# switches_relay.net
KiCad netlist of a schematic drawn in EAGLE
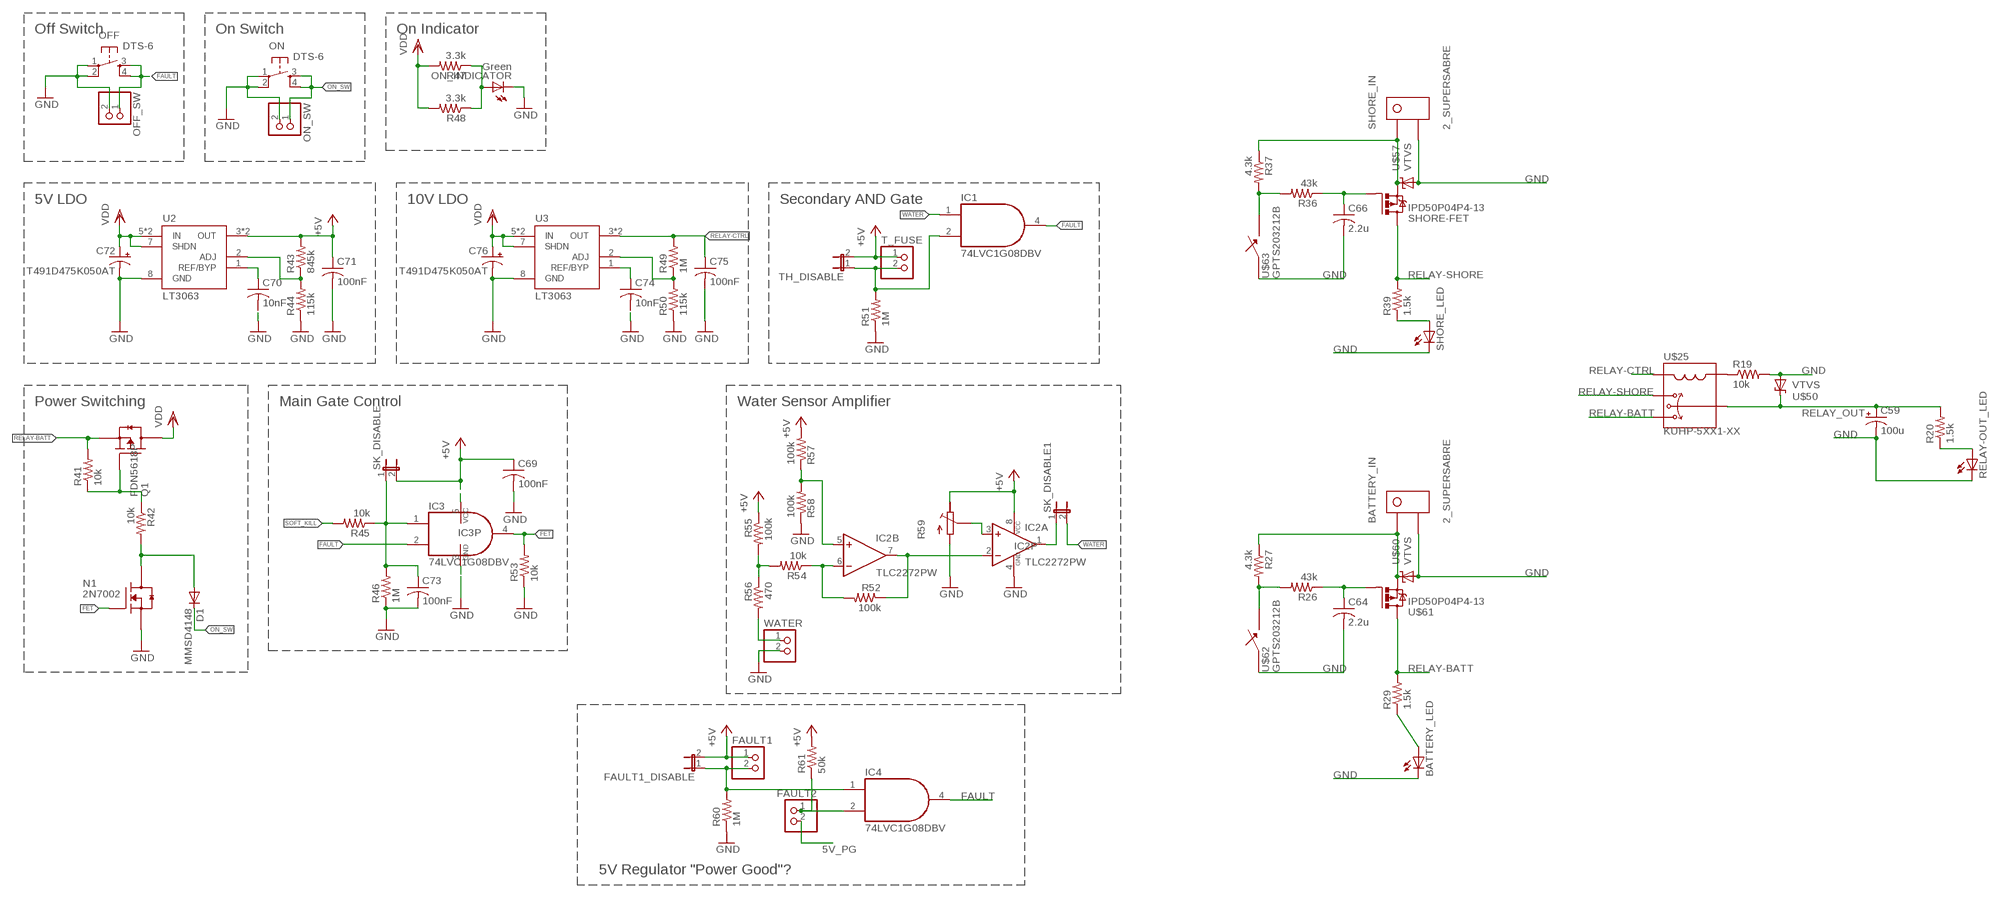
[diagram p0: schematic, sheet 1]

(export (version "E")
  (design (tool "Eeschema 10.0.6"))
  (components
    (comp (ref "BATTERY_IN")
      (value "2_SUPERSABRE")
      (footprint "eagle-import:SUPERSABRE_2CIRCUIT")
      (libsource (lib "eagle-import") (part "2_SUPERSABRE"))
    )
    (comp (ref "BATTERY_LED")
      (value "0805_LED")
      (footprint "eagle-import:0805")
      (libsource (lib "eagle-import") (part "0805_LED"))
    )
    (comp (ref "C59")
      (value "100u")
      (footprint "eagle-import:E3,5-8")
      (libsource (lib "eagle-import") (part "CPOL-USE3.5-8"))
    )
    (comp (ref "C64")
      (value "2.2u")
      (footprint "eagle-import:C0805")
      (libsource (lib "eagle-import") (part "C-USC0805"))
    )
    (comp (ref "C66")
      (value "2.2u")
      (footprint "eagle-import:C0805")
      (libsource (lib "eagle-import") (part "C-USC0805"))
    )
    (comp (ref "C69")
      (value "100nF")
      (footprint "eagle-import:C0805")
      (libsource (lib "eagle-import") (part "C-USC0805"))
    )
    (comp (ref "C70")
      (value "10nF")
      (footprint "eagle-import:C0805")
      (libsource (lib "eagle-import") (part "C-USC0805"))
    )
    (comp (ref "C71")
      (value "100nF")
      (footprint "eagle-import:C0805")
      (libsource (lib "eagle-import") (part "C-USC0805"))
    )
    (comp (ref "C72")
      (value "T491D475K050AT")
      (footprint "eagle-import:CT7343")
      (libsource (lib "eagle-import") (part "CPOL-USCT7343"))
    )
    (comp (ref "C73")
      (value "100nF")
      (footprint "eagle-import:C0805")
      (libsource (lib "eagle-import") (part "C-USC0805"))
    )
    (comp (ref "C74")
      (value "10nF")
      (footprint "eagle-import:C0805")
      (libsource (lib "eagle-import") (part "C-USC0805"))
    )
    (comp (ref "C75")
      (value "100nF")
      (footprint "eagle-import:C0805")
      (libsource (lib "eagle-import") (part "C-USC0805"))
    )
    (comp (ref "C76")
      (value "T491D475K050AT")
      (footprint "eagle-import:CT7343")
      (libsource (lib "eagle-import") (part "CPOL-USCT7343"))
    )
    (comp (ref "D1")
      (value "MMSD4148")
      (footprint "eagle-import:SOD123")
      (libsource (lib "eagle-import") (part "DIODE-SOD123"))
    )
    (comp (ref "FAULT1")
      (value "PINHD-1X2")
      (footprint "eagle-import:1X02")
      (libsource (lib "eagle-import") (part "PINHD-1X2"))
    )
    (comp (ref "FAULT1_DISABLE")
      (value "JP1E")
      (footprint "eagle-import:JP1")
      (libsource (lib "eagle-import") (part "JP1E"))
    )
    (comp (ref "FAULT2")
      (value "PINHD-1X2")
      (footprint "eagle-import:1X02")
      (libsource (lib "eagle-import") (part "PINHD-1X2"))
    )
    (comp (ref "IC1")
      (value "74LVC1G08DBV")
      (footprint "eagle-import:SOT23-5")
      (libsource (lib "eagle-import") (part "741G08DBVLVC"))
    )
    (comp (ref "IC2")
      (value "TLC2272PW")
      (footprint "eagle-import:TSSOP8")
      (libsource (lib "eagle-import") (part "TLC2272PW"))
    )
    (comp (ref "IC3")
      (value "74LVC1G08DBV")
      (footprint "eagle-import:SOT23-5")
      (libsource (lib "eagle-import") (part "741G08DBVLVC"))
    )
    (comp (ref "IC4")
      (value "74LVC1G08DBV")
      (footprint "eagle-import:SOT23-5")
      (libsource (lib "eagle-import") (part "741G08DBVLVC"))
    )
    (comp (ref "N1")
      (value "2N7002")
      (footprint "eagle-import:SOT23")
      (libsource (lib "eagle-import") (part "2N7002"))
    )
    (comp (ref "OFF")
      (value "DTS-6")
      (footprint "eagle-import:DTS-6")
      (libsource (lib "eagle-import") (part "DTS-6"))
    )
    (comp (ref "OFF_SW")
      (value "PINHD-1X2")
      (footprint "eagle-import:1X02")
      (libsource (lib "eagle-import") (part "PINHD-1X2"))
    )
    (comp (ref "ON")
      (value "DTS-6")
      (footprint "eagle-import:DTS-6")
      (libsource (lib "eagle-import") (part "DTS-6"))
    )
    (comp (ref "ON_INDICATOR")
      (value "Green")
      (footprint "eagle-import:CHIP-LED0805")
      (libsource (lib "eagle-import") (part "LEDCHIP-LED0805"))
    )
    (comp (ref "ON_SW")
      (value "PINHD-1X2")
      (footprint "eagle-import:1X02")
      (libsource (lib "eagle-import") (part "PINHD-1X2"))
    )
    (comp (ref "Q1")
      (value "FDN5618P")
      (footprint "eagle-import:SOT23")
      (libsource (lib "eagle-import") (part "FDN5618P"))
    )
    (comp (ref "R19")
      (value "10k")
      (footprint "eagle-import:R0805")
      (libsource (lib "eagle-import") (part "R-US_R0805"))
    )
    (comp (ref "R20")
      (value "1.5k")
      (footprint "eagle-import:R0805")
      (libsource (lib "eagle-import") (part "R-US_R0805"))
    )
    (comp (ref "R26")
      (value "43k")
      (footprint "eagle-import:R0805")
      (libsource (lib "eagle-import") (part "R-US_R0805"))
    )
    (comp (ref "R27")
      (value "4.3k")
      (footprint "eagle-import:R0805")
      (libsource (lib "eagle-import") (part "R-US_R0805"))
    )
    (comp (ref "R29")
      (value "1.5k")
      (footprint "eagle-import:R0805")
      (libsource (lib "eagle-import") (part "R-US_R0805"))
    )
    (comp (ref "R36")
      (value "43k")
      (footprint "eagle-import:R0805")
      (libsource (lib "eagle-import") (part "R-US_R0805"))
    )
    (comp (ref "R37")
      (value "4.3k")
      (footprint "eagle-import:R0805")
      (libsource (lib "eagle-import") (part "R-US_R0805"))
    )
    (comp (ref "R39")
      (value "1.5k")
      (footprint "eagle-import:R0805")
      (libsource (lib "eagle-import") (part "R-US_R0805"))
    )
    (comp (ref "R41")
      (value "10k")
      (footprint "eagle-import:R0805")
      (libsource (lib "eagle-import") (part "R-US_R0805"))
    )
    (comp (ref "R42")
      (value "10k")
      (footprint "eagle-import:R0805")
      (libsource (lib "eagle-import") (part "R-US_R0805"))
    )
    (comp (ref "R43")
      (value "845k")
      (footprint "eagle-import:R0805")
      (libsource (lib "eagle-import") (part "R-US_R0805"))
    )
    (comp (ref "R44")
      (value "115k")
      (footprint "eagle-import:R0805")
      (libsource (lib "eagle-import") (part "R-US_R0805"))
    )
    (comp (ref "R45")
      (value "10k")
      (footprint "eagle-import:R0805")
      (libsource (lib "eagle-import") (part "R-US_R0805"))
    )
    (comp (ref "R46")
      (value "1M")
      (footprint "eagle-import:R0805")
      (libsource (lib "eagle-import") (part "R-US_R0805"))
    )
    (comp (ref "R47")
      (value "3.3k")
      (footprint "eagle-import:R0805")
      (libsource (lib "eagle-import") (part "R-US_R0805"))
    )
    (comp (ref "R48")
      (value "3.3k")
      (footprint "eagle-import:R0805")
      (libsource (lib "eagle-import") (part "R-US_R0805"))
    )
    (comp (ref "R49")
      (value "1M")
      (footprint "eagle-import:R0805")
      (libsource (lib "eagle-import") (part "R-US_R0805"))
    )
    (comp (ref "R50")
      (value "115k")
      (footprint "eagle-import:R0805")
      (libsource (lib "eagle-import") (part "R-US_R0805"))
    )
    (comp (ref "R51")
      (value "1M")
      (footprint "eagle-import:R0805")
      (libsource (lib "eagle-import") (part "R-US_R0805"))
    )
    (comp (ref "R52")
      (value "100k")
      (footprint "eagle-import:R0805")
      (libsource (lib "eagle-import") (part "R-US_R0805"))
    )
    (comp (ref "R53")
      (value "10k")
      (footprint "eagle-import:R0805")
      (libsource (lib "eagle-import") (part "R-US_R0805"))
    )
    (comp (ref "R54")
      (value "10k")
      (footprint "eagle-import:R0805")
      (libsource (lib "eagle-import") (part "R-US_R0805"))
    )
    (comp (ref "R55")
      (value "100k")
      (footprint "eagle-import:R0805")
      (libsource (lib "eagle-import") (part "R-US_R0805"))
    )
    (comp (ref "R56")
      (value "470")
      (footprint "eagle-import:R0805")
      (libsource (lib "eagle-import") (part "R-US_R0805"))
    )
    (comp (ref "R57")
      (value "100k")
      (footprint "eagle-import:R0805")
      (libsource (lib "eagle-import") (part "R-US_R0805"))
    )
    (comp (ref "R58")
      (value "100k")
      (footprint "eagle-import:R0805")
      (libsource (lib "eagle-import") (part "R-US_R0805"))
    )
    (comp (ref "R59")
      (value "R-TRIMM3314J")
      (footprint "eagle-import:RTRIM3314J")
      (libsource (lib "eagle-import") (part "R-TRIMM3314J"))
    )
    (comp (ref "R60")
      (value "1M")
      (footprint "eagle-import:R0805")
      (libsource (lib "eagle-import") (part "R-US_R0805"))
    )
    (comp (ref "R61")
      (value "50k")
      (footprint "eagle-import:R0805")
      (libsource (lib "eagle-import") (part "R-US_R0805"))
    )
    (comp (ref "RELAY-OUT_LED")
      (value "0805_LED")
      (footprint "eagle-import:0805")
      (libsource (lib "eagle-import") (part "0805_LED"))
    )
    (comp (ref "SHORE-FET")
      (value "IPD50P04P4-13")
      (footprint "eagle-import:TO252-3")
      (libsource (lib "eagle-import") (part "IPD50P04P4-13"))
    )
    (comp (ref "SHORE_IN")
      (value "2_SUPERSABRE")
      (footprint "eagle-import:SUPERSABRE_2CIRCUIT")
      (libsource (lib "eagle-import") (part "2_SUPERSABRE"))
    )
    (comp (ref "SHORE_LED")
      (value "0805_LED")
      (footprint "eagle-import:0805")
      (libsource (lib "eagle-import") (part "0805_LED"))
    )
    (comp (ref "SK_DISABLE")
      (value "JP1E")
      (footprint "eagle-import:JP1")
      (libsource (lib "eagle-import") (part "JP1E"))
    )
    (comp (ref "SK_DISABLE1")
      (value "JP1E")
      (footprint "eagle-import:JP1")
      (libsource (lib "eagle-import") (part "JP1E"))
    )
    (comp (ref "TH_DISABLE")
      (value "JP1E")
      (footprint "eagle-import:JP1")
      (libsource (lib "eagle-import") (part "JP1E"))
    )
    (comp (ref "T_FUSE")
      (value "PINHD-1X2")
      (footprint "eagle-import:1X02")
      (libsource (lib "eagle-import") (part "PINHD-1X2"))
    )
    (comp (ref "U$25")
      (value "KUHP-5XX1-XX")
      (footprint "eagle-import:KUHP_6.35MM-QUICK-CONNECT")
      (libsource (lib "eagle-import") (part "KUHP-5XX1-XX"))
    )
    (comp (ref "U$50")
      (value "VTVS")
      (footprint "eagle-import:DO-219AB")
      (libsource (lib "eagle-import") (part "VTVS"))
    )
    (comp (ref "U$57")
      (value "VTVS")
      (footprint "eagle-import:DO-219AB")
      (libsource (lib "eagle-import") (part "VTVS"))
    )
    (comp (ref "U$60")
      (value "VTVS")
      (footprint "eagle-import:DO-219AB")
      (libsource (lib "eagle-import") (part "VTVS"))
    )
    (comp (ref "U$61")
      (value "IPD50P04P4-13")
      (footprint "eagle-import:TO252-3")
      (libsource (lib "eagle-import") (part "IPD50P04P4-13"))
    )
    (comp (ref "U$62")
      (value "GPTS203212B")
      (footprint "eagle-import:GPTS203211B")
      (libsource (lib "eagle-import") (part "GPTS203212B"))
    )
    (comp (ref "U$63")
      (value "GPTS203212B")
      (footprint "eagle-import:GPTS203211B")
      (libsource (lib "eagle-import") (part "GPTS203212B"))
    )
    (comp (ref "U2")
      (value "LT3063")
      (footprint "eagle-import:MSOP8")
      (libsource (lib "eagle-import") (part "LT3063"))
    )
    (comp (ref "U3")
      (value "LT3063")
      (footprint "eagle-import:MSOP8")
      (libsource (lib "eagle-import") (part "LT3063"))
    )
    (comp (ref "WATER")
      (value "PINHD-1X2")
      (footprint "eagle-import:1X02")
      (libsource (lib "eagle-import") (part "PINHD-1X2"))
    )
  )
  (nets
    (net (code "1") (name "+5V") (class "Default")
      (node (ref "C69") (pin "1") (pinfunction "1_1") (pintype "passive"))
      (node (ref "C71") (pin "1") (pinfunction "1_1") (pintype "passive"))
      (node (ref "FAULT1") (pin "1") (pinfunction "1_1") (pintype "passive"))
      (node (ref "FAULT1_DISABLE") (pin "2") (pinfunction "2_2") (pintype "passive"))
      (node (ref "IC2") (pin "8") (pinfunction "VCC_8") (pintype "power_in"))
      (node (ref "IC3") (pin "5") (pinfunction "VCC_5") (pintype "power_in"))
      (node (ref "R43") (pin "2") (pinfunction "2_2") (pintype "passive"))
      (node (ref "R55") (pin "1") (pinfunction "1_1") (pintype "passive"))
      (node (ref "R57") (pin "2") (pinfunction "2_2") (pintype "passive"))
      (node (ref "R59") (pin "3") (pinfunction "A_3") (pintype "passive"))
      (node (ref "R61") (pin "2") (pinfunction "2_2") (pintype "passive"))
      (node (ref "SK_DISABLE") (pin "2") (pinfunction "2_2") (pintype "passive"))
      (node (ref "TH_DISABLE") (pin "2") (pinfunction "2_2") (pintype "passive"))
      (node (ref "T_FUSE") (pin "1") (pinfunction "1_1") (pintype "passive"))
      (node (ref "U2") (pin "3") (pinfunction "OUT_3") (pintype "bidirectional"))
      (node (ref "U2") (pin "4") (pinfunction "OUT_4") (pintype "bidirectional"))
    )
    (net (code "2") (name "/5V_PG") (class "Default")
      (node (ref "FAULT2") (pin "2") (pinfunction "2_2") (pintype "passive"))
    )
    (net (code "3") (name "/RELAY-SHORE") (class "Default")
      (node (ref "R39") (pin "2") (pinfunction "2_2") (pintype "passive"))
      (node (ref "SHORE-FET") (pin "3") (pinfunction "S_3") (pintype "passive"))
      (node (ref "U$25") (pin "2A") (pinfunction "2_2A") (pintype "bidirectional"))
      (node (ref "U$25") (pin "2B") (pinfunction "2_2B") (pintype "bidirectional"))
    )
    (net (code "4") (name "/RELAY_OUT") (class "Default")
      (node (ref "C59") (pin "+") (pinfunction "+_+") (pintype "passive"))
      (node (ref "R20") (pin "2") (pinfunction "2_2") (pintype "passive"))
      (node (ref "U$25") (pin "7A") (pinfunction "7_7A") (pintype "bidirectional"))
      (node (ref "U$25") (pin "7B") (pinfunction "7_7B") (pintype "bidirectional"))
      (node (ref "U$50") (pin "P$2") (pinfunction "C_P$2") (pintype "passive"))
    )
    (net (code "5") (name "FAULT") (class "Default")
      (node (ref "IC1") (pin "4") (pinfunction "O_4") (pintype "output"))
      (node (ref "IC3") (pin "2") (pinfunction "I1_2") (pintype "input"))
      (node (ref "IC4") (pin "4") (pinfunction "O_4") (pintype "output"))
      (node (ref "OFF") (pin "3") (pinfunction "3_3") (pintype "passive"))
      (node (ref "OFF") (pin "4") (pinfunction "4_4") (pintype "passive"))
      (node (ref "OFF_SW") (pin "1") (pinfunction "1_1") (pintype "passive"))
    )
    (net (code "6") (name "FET") (class "Default")
      (node (ref "IC3") (pin "4") (pinfunction "O_4") (pintype "output"))
      (node (ref "N1") (pin "1") (pinfunction "G_1") (pintype "passive"))
      (node (ref "R53") (pin "2") (pinfunction "2_2") (pintype "passive"))
    )
    (net (code "7") (name "GND") (class "Default")
      (node (ref "BATTERY_IN") (pin "P$2") (pinfunction "P$2_P$2") (pintype "bidirectional"))
      (node (ref "BATTERY_LED") (pin "P$2") (pinfunction "C_P$2") (pintype "passive"))
      (node (ref "C59") (pin "-") (pinfunction "-_-") (pintype "passive"))
      (node (ref "C64") (pin "2") (pinfunction "2_2") (pintype "passive"))
      (node (ref "C66") (pin "2") (pinfunction "2_2") (pintype "passive"))
      (node (ref "C69") (pin "2") (pinfunction "2_2") (pintype "passive"))
      (node (ref "C70") (pin "2") (pinfunction "2_2") (pintype "passive"))
      (node (ref "C71") (pin "2") (pinfunction "2_2") (pintype "passive"))
      (node (ref "C72") (pin "-") (pinfunction "-_-") (pintype "passive"))
      (node (ref "C73") (pin "2") (pinfunction "2_2") (pintype "passive"))
      (node (ref "C74") (pin "2") (pinfunction "2_2") (pintype "passive"))
      (node (ref "C75") (pin "2") (pinfunction "2_2") (pintype "passive"))
      (node (ref "C76") (pin "-") (pinfunction "-_-") (pintype "passive"))
      (node (ref "IC2") (pin "4") (pinfunction "GND_4") (pintype "power_in"))
      (node (ref "IC3") (pin "3") (pinfunction "GND_3") (pintype "power_in"))
      (node (ref "N1") (pin "2") (pinfunction "S_2") (pintype "passive"))
      (node (ref "OFF") (pin "1") (pinfunction "1_1") (pintype "passive"))
      (node (ref "OFF") (pin "2") (pinfunction "2_2") (pintype "passive"))
      (node (ref "OFF_SW") (pin "2") (pinfunction "2_2") (pintype "passive"))
      (node (ref "ON") (pin "1") (pinfunction "1_1") (pintype "passive"))
      (node (ref "ON") (pin "2") (pinfunction "2_2") (pintype "passive"))
      (node (ref "ON_INDICATOR") (pin "C") (pinfunction "C_C") (pintype "passive"))
      (node (ref "ON_SW") (pin "2") (pinfunction "2_2") (pintype "passive"))
      (node (ref "R19") (pin "2") (pinfunction "2_2") (pintype "passive"))
      (node (ref "R44") (pin "1") (pinfunction "1_1") (pintype "passive"))
      (node (ref "R46") (pin "1") (pinfunction "1_1") (pintype "passive"))
      (node (ref "R50") (pin "1") (pinfunction "1_1") (pintype "passive"))
      (node (ref "R51") (pin "1") (pinfunction "1_1") (pintype "passive"))
      (node (ref "R53") (pin "1") (pinfunction "1_1") (pintype "passive"))
      (node (ref "R58") (pin "1") (pinfunction "1_1") (pintype "passive"))
      (node (ref "R59") (pin "1") (pinfunction "E_1") (pintype "passive"))
      (node (ref "R60") (pin "1") (pinfunction "1_1") (pintype "passive"))
      (node (ref "RELAY-OUT_LED") (pin "P$2") (pinfunction "C_P$2") (pintype "passive"))
      (node (ref "SHORE_IN") (pin "P$2") (pinfunction "P$2_P$2") (pintype "bidirectional"))
      (node (ref "SHORE_LED") (pin "P$2") (pinfunction "C_P$2") (pintype "passive"))
      (node (ref "U$50") (pin "P$1") (pinfunction "A_P$1") (pintype "passive"))
      (node (ref "U$57") (pin "P$1") (pinfunction "A_P$1") (pintype "passive"))
      (node (ref "U$60") (pin "P$1") (pinfunction "A_P$1") (pintype "passive"))
      (node (ref "U$62") (pin "P$1") (pinfunction "P$1_P$1") (pintype "bidirectional"))
      (node (ref "U$63") (pin "P$1") (pinfunction "P$1_P$1") (pintype "bidirectional"))
      (node (ref "U2") (pin "8") (pinfunction "GND_8") (pintype "bidirectional"))
      (node (ref "U3") (pin "8") (pinfunction "GND_8") (pintype "bidirectional"))
      (node (ref "WATER") (pin "2") (pinfunction "2_2") (pintype "passive"))
    )
    (net (code "8") (name "Net-(BATTERY_LED-A)") (class "Default")
      (node (ref "BATTERY_LED") (pin "P$1") (pinfunction "A_P$1") (pintype "passive"))
      (node (ref "R29") (pin "1") (pinfunction "1_1") (pintype "passive"))
    )
    (net (code "9") (name "Net-(IC1A-I1)") (class "Default")
      (node (ref "IC1") (pin "2") (pinfunction "I1_2") (pintype "input"))
      (node (ref "R51") (pin "2") (pinfunction "2_2") (pintype "passive"))
      (node (ref "TH_DISABLE") (pin "1") (pinfunction "1_1") (pintype "passive"))
      (node (ref "T_FUSE") (pin "2") (pinfunction "2_2") (pintype "passive"))
    )
    (net (code "10") (name "Net-(IC2A-+IN)") (class "Default")
      (node (ref "IC2") (pin "3") (pinfunction "+IN_3") (pintype "input"))
      (node (ref "R59") (pin "2") (pinfunction "S_2") (pintype "passive"))
    )
    (net (code "11") (name "Net-(IC2A--IN)") (class "Default")
      (node (ref "IC2") (pin "2") (pinfunction "-IN_2") (pintype "input"))
      (node (ref "IC2") (pin "7") (pinfunction "OUT_7") (pintype "output"))
      (node (ref "R52") (pin "1") (pinfunction "1_1") (pintype "passive"))
    )
    (net (code "12") (name "Net-(IC2A-OUT)") (class "Default")
      (node (ref "IC2") (pin "1") (pinfunction "OUT_1") (pintype "output"))
      (node (ref "SK_DISABLE1") (pin "1") (pinfunction "1_1") (pintype "passive"))
    )
    (net (code "13") (name "Net-(IC2B-+IN)") (class "Default")
      (node (ref "IC2") (pin "5") (pinfunction "+IN_5") (pintype "input"))
      (node (ref "R57") (pin "1") (pinfunction "1_1") (pintype "passive"))
      (node (ref "R58") (pin "2") (pinfunction "2_2") (pintype "passive"))
    )
    (net (code "14") (name "Net-(IC2B--IN)") (class "Default")
      (node (ref "IC2") (pin "6") (pinfunction "-IN_6") (pintype "input"))
      (node (ref "R52") (pin "2") (pinfunction "2_2") (pintype "passive"))
      (node (ref "R54") (pin "1") (pinfunction "1_1") (pintype "passive"))
    )
    (net (code "15") (name "Net-(IC3A-I0)") (class "Default")
      (node (ref "C73") (pin "1") (pinfunction "1_1") (pintype "passive"))
      (node (ref "IC3") (pin "1") (pinfunction "I0_1") (pintype "input"))
      (node (ref "R45") (pin "1") (pinfunction "1_1") (pintype "passive"))
      (node (ref "R46") (pin "2") (pinfunction "2_2") (pintype "passive"))
      (node (ref "SK_DISABLE") (pin "1") (pinfunction "1_1") (pintype "passive"))
    )
    (net (code "16") (name "Net-(IC4A-I0)") (class "Default")
      (node (ref "FAULT1") (pin "2") (pinfunction "2_2") (pintype "passive"))
      (node (ref "FAULT1_DISABLE") (pin "1") (pinfunction "1_1") (pintype "passive"))
      (node (ref "IC4") (pin "1") (pinfunction "I0_1") (pintype "input"))
      (node (ref "R60") (pin "2") (pinfunction "2_2") (pintype "passive"))
    )
    (net (code "17") (name "Net-(IC4A-I1)") (class "Default")
      (node (ref "FAULT2") (pin "1") (pinfunction "1_1") (pintype "passive"))
      (node (ref "IC4") (pin "2") (pinfunction "I1_2") (pintype "input"))
      (node (ref "R61") (pin "1") (pinfunction "1_1") (pintype "passive"))
    )
    (net (code "18") (name "Net-(N1-D)") (class "Default")
      (node (ref "D1") (pin "A") (pinfunction "A_A") (pintype "passive"))
      (node (ref "N1") (pin "3") (pinfunction "D_3") (pintype "bidirectional"))
      (node (ref "R42") (pin "2") (pinfunction "2_2") (pintype "passive"))
    )
    (net (code "19") (name "Net-(ON_INDICATOR-PadA)") (class "Default")
      (node (ref "ON_INDICATOR") (pin "A") (pinfunction "A_A") (pintype "passive"))
      (node (ref "R47") (pin "1") (pinfunction "1_1") (pintype "passive"))
      (node (ref "R48") (pin "1") (pinfunction "1_1") (pintype "passive"))
    )
    (net (code "20") (name "Net-(Q1-G)") (class "Default")
      (node (ref "Q1") (pin "1") (pinfunction "G_1") (pintype "passive"))
      (node (ref "R41") (pin "1") (pinfunction "1_1") (pintype "passive"))
      (node (ref "R42") (pin "1") (pinfunction "1_1") (pintype "passive"))
    )
    (net (code "21") (name "Net-(R19-Pad1)") (class "Default")
      (node (ref "R19") (pin "1") (pinfunction "1_1") (pintype "passive"))
      (node (ref "U$25") (pin "AA") (pinfunction "A_AA") (pintype "bidirectional"))
      (node (ref "U$25") (pin "AB") (pinfunction "A_AB") (pintype "bidirectional"))
    )
    (net (code "22") (name "Net-(R26-Pad2)") (class "Default")
      (node (ref "R26") (pin "2") (pinfunction "2_2") (pintype "passive"))
      (node (ref "R27") (pin "2") (pinfunction "2_2") (pintype "passive"))
      (node (ref "U$62") (pin "P$2") (pinfunction "P$2_P$2") (pintype "bidirectional"))
    )
    (net (code "23") (name "Net-(R36-Pad2)") (class "Default")
      (node (ref "R36") (pin "2") (pinfunction "2_2") (pintype "passive"))
      (node (ref "R37") (pin "2") (pinfunction "2_2") (pintype "passive"))
      (node (ref "U$63") (pin "P$2") (pinfunction "P$2_P$2") (pintype "bidirectional"))
    )
    (net (code "24") (name "Net-(R54-Pad2)") (class "Default")
      (node (ref "R54") (pin "2") (pinfunction "2_2") (pintype "passive"))
      (node (ref "R55") (pin "2") (pinfunction "2_2") (pintype "passive"))
      (node (ref "R56") (pin "1") (pinfunction "1_1") (pintype "passive"))
    )
    (net (code "25") (name "Net-(R56-Pad2)") (class "Default")
      (node (ref "R56") (pin "2") (pinfunction "2_2") (pintype "passive"))
      (node (ref "WATER") (pin "1") (pinfunction "1_1") (pintype "passive"))
    )
    (net (code "26") (name "Net-(RELAY-OUT_LED-A)") (class "Default")
      (node (ref "R20") (pin "1") (pinfunction "1_1") (pintype "passive"))
      (node (ref "RELAY-OUT_LED") (pin "P$1") (pinfunction "A_P$1") (pintype "passive"))
    )
    (net (code "27") (name "Net-(SHORE-FET-D)") (class "Default")
      (node (ref "R37") (pin "1") (pinfunction "1_1") (pintype "passive"))
      (node (ref "SHORE-FET") (pin "TAB") (pinfunction "D_TAB") (pintype "passive"))
      (node (ref "SHORE_IN") (pin "P$1") (pinfunction "P$1_P$1") (pintype "bidirectional"))
      (node (ref "U$57") (pin "P$2") (pinfunction "C_P$2") (pintype "passive"))
    )
    (net (code "28") (name "Net-(SHORE-FET-G)") (class "Default")
      (node (ref "C66") (pin "1") (pinfunction "1_1") (pintype "passive"))
      (node (ref "R36") (pin "1") (pinfunction "1_1") (pintype "passive"))
      (node (ref "SHORE-FET") (pin "1") (pinfunction "G_1") (pintype "passive"))
    )
    (net (code "29") (name "Net-(SHORE_LED-A)") (class "Default")
      (node (ref "R39") (pin "1") (pinfunction "1_1") (pintype "passive"))
      (node (ref "SHORE_LED") (pin "P$1") (pinfunction "A_P$1") (pintype "passive"))
    )
    (net (code "30") (name "Net-(U$60-C)") (class "Default")
      (node (ref "BATTERY_IN") (pin "P$1") (pinfunction "P$1_P$1") (pintype "bidirectional"))
      (node (ref "R27") (pin "1") (pinfunction "1_1") (pintype "passive"))
      (node (ref "U$60") (pin "P$2") (pinfunction "C_P$2") (pintype "passive"))
      (node (ref "U$61") (pin "TAB") (pinfunction "D_TAB") (pintype "passive"))
    )
    (net (code "31") (name "Net-(U$61-G)") (class "Default")
      (node (ref "C64") (pin "1") (pinfunction "1_1") (pintype "passive"))
      (node (ref "R26") (pin "1") (pinfunction "1_1") (pintype "passive"))
      (node (ref "U$61") (pin "1") (pinfunction "G_1") (pintype "passive"))
    )
    (net (code "32") (name "Net-(U2-ADJ)") (class "Default")
      (node (ref "R43") (pin "1") (pinfunction "1_1") (pintype "passive"))
      (node (ref "R44") (pin "2") (pinfunction "2_2") (pintype "passive"))
      (node (ref "U2") (pin "2") (pinfunction "ADJ_2") (pintype "bidirectional"))
    )
    (net (code "33") (name "Net-(U2-REF{slash}BYP)") (class "Default")
      (node (ref "C70") (pin "1") (pinfunction "1_1") (pintype "passive"))
      (node (ref "U2") (pin "1") (pinfunction "REF/BYP_1") (pintype "bidirectional"))
    )
    (net (code "34") (name "Net-(U3-ADJ)") (class "Default")
      (node (ref "R49") (pin "1") (pinfunction "1_1") (pintype "passive"))
      (node (ref "R50") (pin "2") (pinfunction "2_2") (pintype "passive"))
      (node (ref "U3") (pin "2") (pinfunction "ADJ_2") (pintype "bidirectional"))
    )
    (net (code "35") (name "Net-(U3-REF{slash}BYP)") (class "Default")
      (node (ref "C74") (pin "1") (pinfunction "1_1") (pintype "passive"))
      (node (ref "U3") (pin "1") (pinfunction "REF/BYP_1") (pintype "bidirectional"))
    )
    (net (code "36") (name "ON_SW") (class "Default")
      (node (ref "D1") (pin "C") (pinfunction "C_C") (pintype "passive"))
      (node (ref "ON") (pin "3") (pinfunction "3_3") (pintype "passive"))
      (node (ref "ON") (pin "4") (pinfunction "4_4") (pintype "passive"))
      (node (ref "ON_SW") (pin "1") (pinfunction "1_1") (pintype "passive"))
    )
    (net (code "37") (name "RELAY-BATT") (class "Default")
      (node (ref "Q1") (pin "2") (pinfunction "S_2") (pintype "passive"))
      (node (ref "R29") (pin "2") (pinfunction "2_2") (pintype "passive"))
      (node (ref "R41") (pin "2") (pinfunction "2_2") (pintype "passive"))
      (node (ref "U$25") (pin "5A") (pinfunction "5_5A") (pintype "bidirectional"))
      (node (ref "U$25") (pin "5B") (pinfunction "5_5B") (pintype "bidirectional"))
      (node (ref "U$61") (pin "3") (pinfunction "S_3") (pintype "passive"))
    )
    (net (code "38") (name "RELAY-CTRL") (class "Default")
      (node (ref "C75") (pin "1") (pinfunction "1_1") (pintype "passive"))
      (node (ref "R49") (pin "2") (pinfunction "2_2") (pintype "passive"))
      (node (ref "U$25") (pin "BA") (pinfunction "B_BA") (pintype "bidirectional"))
      (node (ref "U$25") (pin "BB") (pinfunction "B_BB") (pintype "bidirectional"))
      (node (ref "U3") (pin "3") (pinfunction "OUT_3") (pintype "bidirectional"))
      (node (ref "U3") (pin "4") (pinfunction "OUT_4") (pintype "bidirectional"))
    )
    (net (code "39") (name "SOFT_KILL") (class "Default")
      (node (ref "R45") (pin "2") (pinfunction "2_2") (pintype "passive"))
    )
    (net (code "40") (name "VDD") (class "Default")
      (node (ref "C72") (pin "+") (pinfunction "+_+") (pintype "passive"))
      (node (ref "C76") (pin "+") (pinfunction "+_+") (pintype "passive"))
      (node (ref "Q1") (pin "3") (pinfunction "D_3") (pintype "passive"))
      (node (ref "R47") (pin "2") (pinfunction "2_2") (pintype "passive"))
      (node (ref "R48") (pin "2") (pinfunction "2_2") (pintype "passive"))
      (node (ref "U2") (pin "5") (pinfunction "IN_5") (pintype "bidirectional"))
      (node (ref "U2") (pin "6") (pinfunction "IN_6") (pintype "bidirectional"))
      (node (ref "U2") (pin "7") (pinfunction "SHDN_7") (pintype "bidirectional"))
      (node (ref "U3") (pin "5") (pinfunction "IN_5") (pintype "bidirectional"))
      (node (ref "U3") (pin "6") (pinfunction "IN_6") (pintype "bidirectional"))
      (node (ref "U3") (pin "7") (pinfunction "SHDN_7") (pintype "bidirectional"))
    )
    (net (code "41") (name "WATER") (class "Default")
      (node (ref "IC1") (pin "1") (pinfunction "I0_1") (pintype "input"))
      (node (ref "SK_DISABLE1") (pin "2") (pinfunction "2_2") (pintype "passive"))
    )
  )
)
